# led.net
KiCad netlist of a schematic drawn in Altium Designer
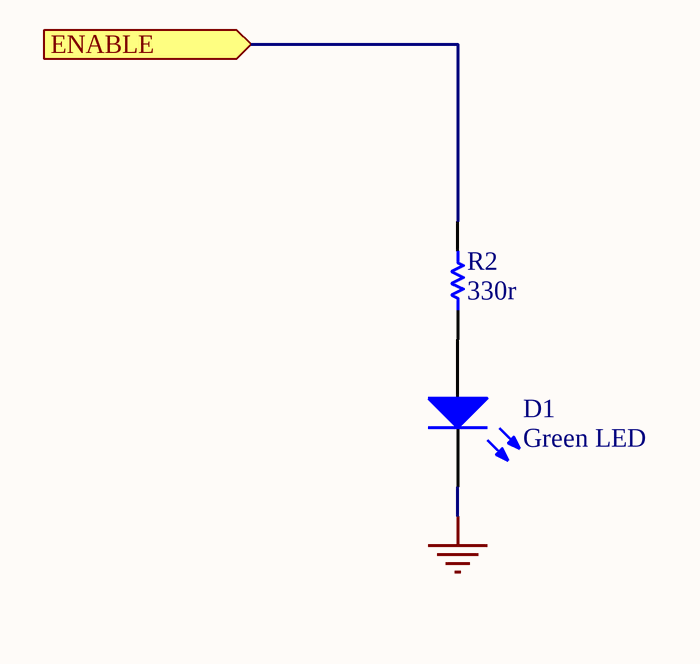
[diagram p0: led.SchDoc]

(export (version "E")
  (design (tool "Eeschema 10.0.6"))
  (components
    (comp (ref "D1")
      (value "Green LED")
      (footprint "LED 0805")
      (description "Typical INFRARED GaAs LED")
      (fields (field (name "PUBLISHER") "Altium Limited"))
      (libsource (lib "Miscellaneous Devices") (part "LED2"))
    )
    (comp (ref "R2")
      (value "330r")
      (footprint "RESC1608N")
      (description "Resistor")
      (fields (field (name "PUBLISHER") "Altium Limited"))
      (libsource (lib "Miscellaneous Devices") (part "Res1"))
    )
  )
  (nets
    (net (code "1") (name "/ENABLE") (class "Default")
      (node (ref "R2") (pin "2") (pinfunction "2_2") (pintype "passive"))
    )
    (net (code "2") (name "GND") (class "Default")
      (node (ref "D1") (pin "2") (pinfunction "K_2") (pintype "passive"))
    )
    (net (code "3") (name "Net-(D1-A)") (class "Default")
      (node (ref "D1") (pin "1") (pinfunction "A_1") (pintype "passive"))
      (node (ref "R2") (pin "1") (pinfunction "1_1") (pintype "passive"))
    )
  )
)
